# Pinguino4550.net
KiCad netlist of a schematic drawn in EAGLE
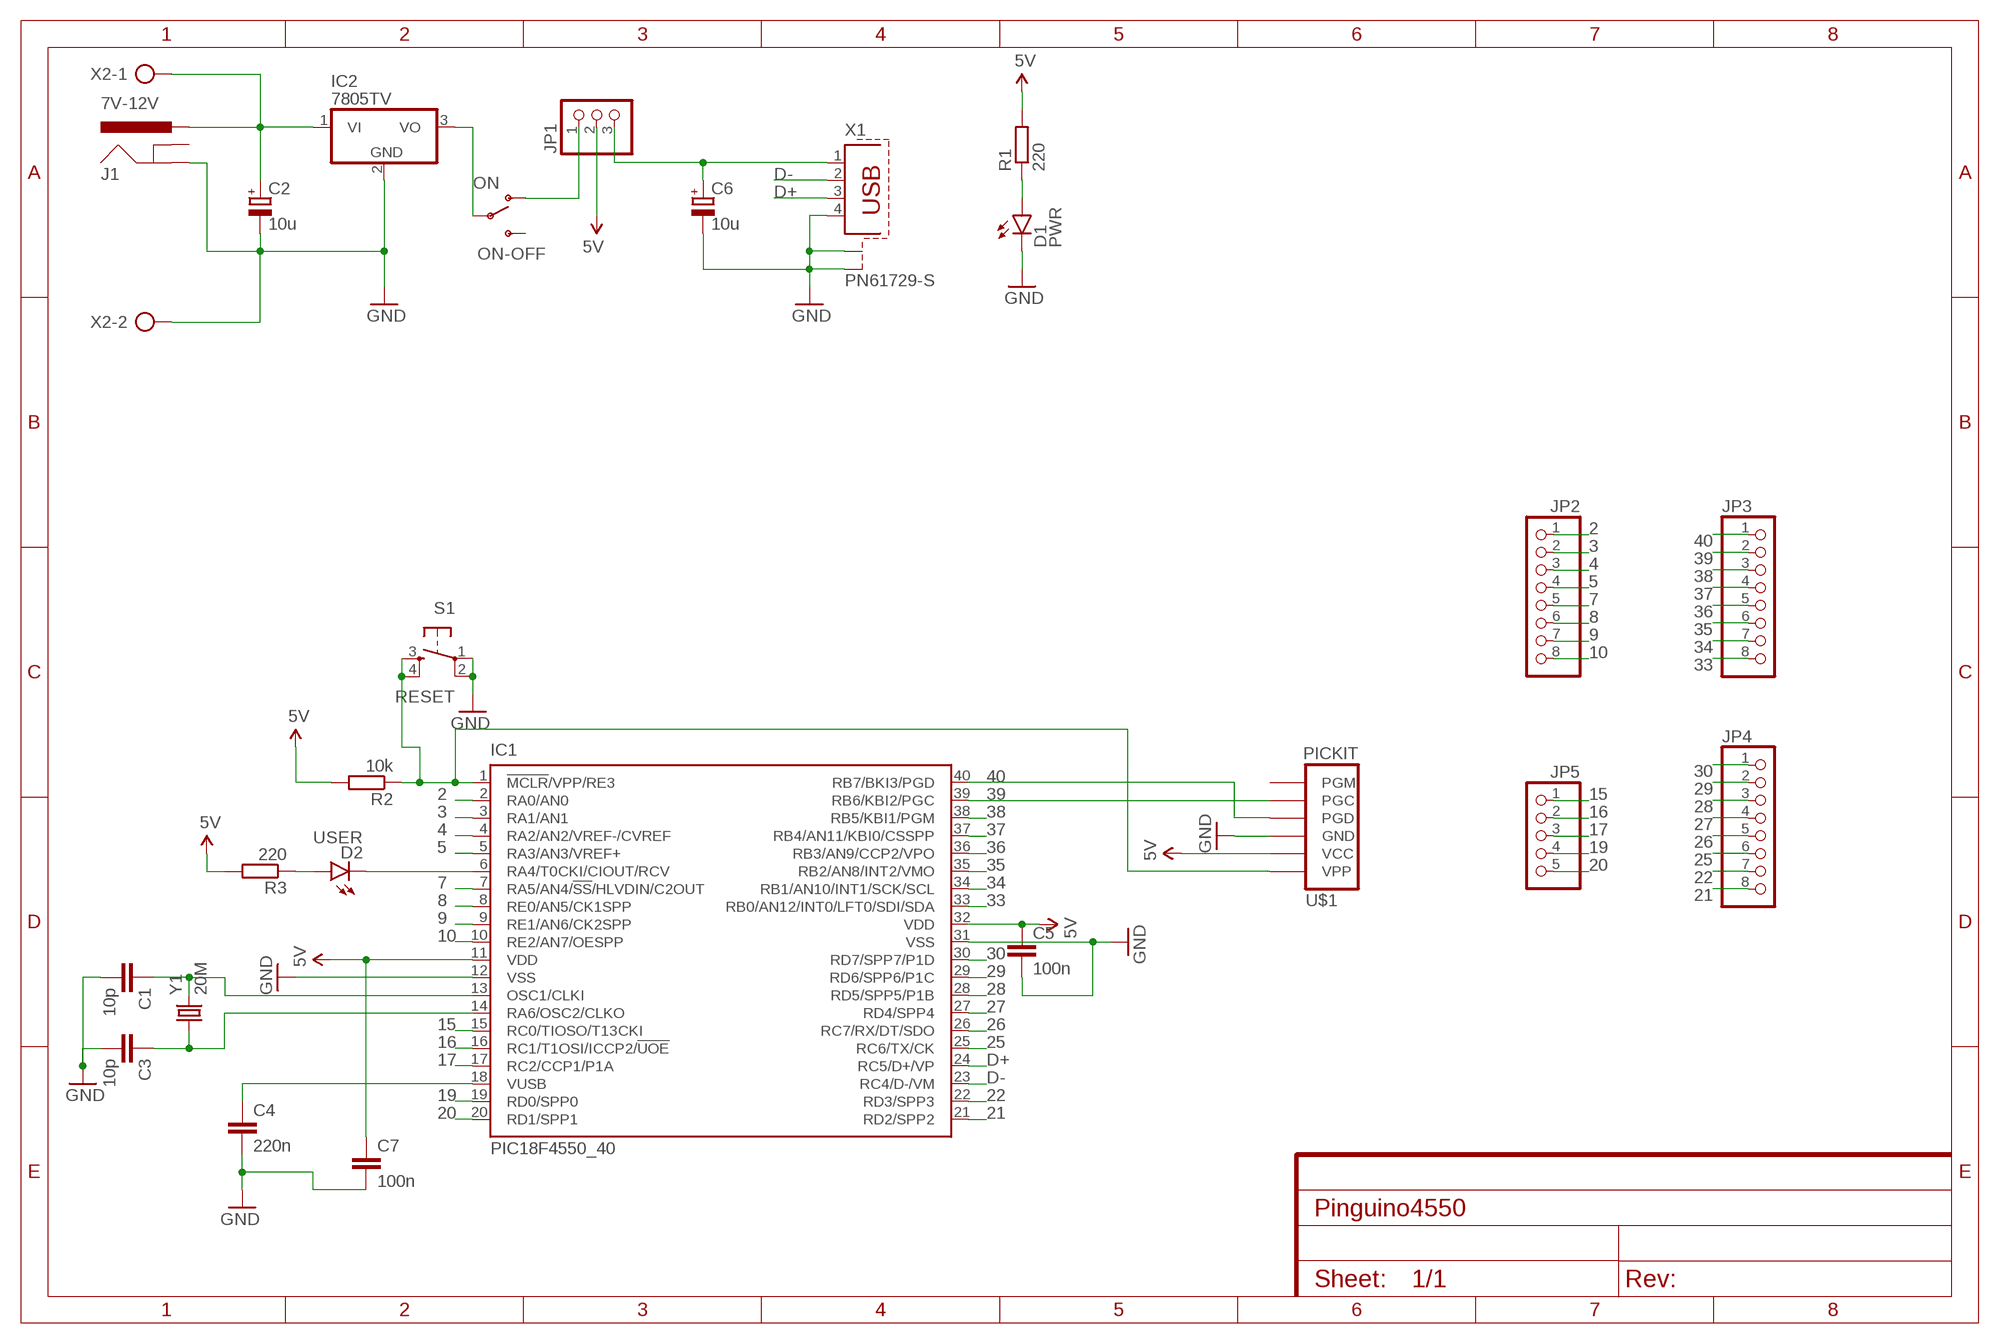
[diagram p0: schematic, sheet 1]

(export (version "E")
  (design (tool "Eeschema 10.0.6"))
  (components
    (comp (ref "C1")
      (value "10p")
      (footprint "eagle-import:C025-030X050")
      (libsource (lib "eagle-import") (part "C-EU025-030X050"))
    )
    (comp (ref "C2")
      (value "10u")
      (footprint "eagle-import:E2,5-5")
      (libsource (lib "eagle-import") (part "CPOL-EUE2.5-5"))
    )
    (comp (ref "C3")
      (value "10p")
      (footprint "eagle-import:C025-030X050")
      (libsource (lib "eagle-import") (part "C-EU025-030X050"))
    )
    (comp (ref "C4")
      (value "220n")
      (footprint "eagle-import:C025-030X050")
      (libsource (lib "eagle-import") (part "C-EU025-030X050"))
    )
    (comp (ref "C5")
      (value "100n")
      (footprint "eagle-import:C025-030X050")
      (libsource (lib "eagle-import") (part "C-EU025-030X050"))
    )
    (comp (ref "C6")
      (value "10u")
      (footprint "eagle-import:E2,5-5")
      (libsource (lib "eagle-import") (part "CPOL-EUE2.5-5"))
    )
    (comp (ref "C7")
      (value "100n")
      (footprint "eagle-import:C025-030X050")
      (libsource (lib "eagle-import") (part "C-EU025-030X050"))
    )
    (comp (ref "D1")
      (value "PWR")
      (footprint "eagle-import:LED5MM")
      (libsource (lib "eagle-import") (part "LED5MM"))
    )
    (comp (ref "D2")
      (value "USER")
      (footprint "eagle-import:LED5MM")
      (libsource (lib "eagle-import") (part "LED5MM"))
    )
    (comp (ref "IC1")
      (value "PIC18F4550_40")
      (footprint "eagle-import:DIL40")
      (fields (field (name "MF") "MICROCHIP") (field (name "MPN") "PIC18F4550-I/P"))
      (libsource (lib "eagle-import") (part "PIC18F4_40550"))
    )
    (comp (ref "IC2")
      (value "7805TV")
      (footprint "eagle-import:TO220V")
      (libsource (lib "eagle-import") (part "78TV05"))
    )
    (comp (ref "J1")
      (value "7V-12V")
      (footprint "eagle-import:POWER_JACK_SLOT")
      (libsource (lib "eagle-import") (part "POWER_JACKSLT"))
    )
    (comp (ref "JP1")
      (value "PINHD-1X3")
      (footprint "eagle-import:1X03")
      (libsource (lib "eagle-import") (part "PINHD-1X3"))
    )
    (comp (ref "JP2")
      (value "PINHD-1X8")
      (footprint "eagle-import:1X08")
      (libsource (lib "eagle-import") (part "PINHD-1X8"))
    )
    (comp (ref "JP3")
      (value "PINHD-1X8")
      (footprint "eagle-import:1X08")
      (libsource (lib "eagle-import") (part "PINHD-1X8"))
    )
    (comp (ref "JP4")
      (value "PINHD-1X8")
      (footprint "eagle-import:1X08")
      (libsource (lib "eagle-import") (part "PINHD-1X8"))
    )
    (comp (ref "JP5")
      (value "PINHD-1X5")
      (footprint "eagle-import:1X05")
      (libsource (lib "eagle-import") (part "PINHD-1X5"))
    )
    (comp (ref "ON-OFF")
      (value "ON")
      (footprint "eagle-import:SWITCH-SPDT")
      (libsource (lib "eagle-import") (part "SWITCH-SPDTPTH"))
    )
    (comp (ref "R1")
      (value "220")
      (footprint "eagle-import:0207_7")
      (libsource (lib "eagle-import") (part "R-EU_0207/7"))
    )
    (comp (ref "R2")
      (value "10k")
      (footprint "eagle-import:0207_7")
      (libsource (lib "eagle-import") (part "R-EU_0207/7"))
    )
    (comp (ref "R3")
      (value "220")
      (footprint "eagle-import:0207_7")
      (libsource (lib "eagle-import") (part "R-EU_0207/7"))
    )
    (comp (ref "S1")
      (value "RESET")
      (footprint "eagle-import:TACTILE-PTH")
      (libsource (lib "eagle-import") (part "TAC_SWITCHPTH"))
    )
    (comp (ref "U$1")
      (value "PICKIT")
      (footprint "eagle-import:MOLEX-1X6_LOCK")
      (libsource (lib "eagle-import") (part "PIC-ICSPPOLAR_LOCK"))
    )
    (comp (ref "X1")
      (value "PN61729-S")
      (footprint "eagle-import:PN61729-S")
      (libsource (lib "eagle-import") (part "PN61729-S"))
    )
    (comp (ref "X2")
      (value "AK500/2")
      (footprint "eagle-import:AK500_2")
      (libsource (lib "eagle-import") (part "AK500/2"))
    )
    (comp (ref "Y1")
      (value "20M")
      (footprint "eagle-import:HC49US")
      (libsource (lib "eagle-import") (part "CRYSTALHC49US"))
    )
  )
  (nets
    (net (code "1") (name "/2") (class "Default")
      (node (ref "IC1") (pin "2") (pinfunction "RA0/AN0_2") (pintype "bidirectional"))
      (node (ref "JP2") (pin "1") (pinfunction "1_1") (pintype "passive"))
    )
    (net (code "2") (name "/3") (class "Default")
      (node (ref "IC1") (pin "3") (pinfunction "RA1/AN1_3") (pintype "bidirectional"))
      (node (ref "JP2") (pin "2") (pinfunction "2_2") (pintype "passive"))
    )
    (net (code "3") (name "/4") (class "Default")
      (node (ref "IC1") (pin "4") (pinfunction "RA2/AN2/VREF-/CVREF_4") (pintype "bidirectional"))
      (node (ref "JP2") (pin "3") (pinfunction "3_3") (pintype "passive"))
    )
    (net (code "4") (name "/5") (class "Default")
      (node (ref "IC1") (pin "5") (pinfunction "RA3/AN3/VREF+_5") (pintype "bidirectional"))
      (node (ref "JP2") (pin "4") (pinfunction "4_4") (pintype "passive"))
    )
    (net (code "5") (name "/7") (class "Default")
      (node (ref "IC1") (pin "7") (pinfunction "RA5/AN4/~{SS}/HLVDIN/C2OUT_7") (pintype "bidirectional"))
      (node (ref "JP2") (pin "5") (pinfunction "5_5") (pintype "passive"))
    )
    (net (code "6") (name "/8") (class "Default")
      (node (ref "IC1") (pin "8") (pinfunction "RE0/AN5/CK1SPP_8") (pintype "bidirectional"))
      (node (ref "JP2") (pin "6") (pinfunction "6_6") (pintype "passive"))
    )
    (net (code "7") (name "/9") (class "Default")
      (node (ref "IC1") (pin "9") (pinfunction "RE1/AN6/CK2SPP_9") (pintype "bidirectional"))
      (node (ref "JP2") (pin "7") (pinfunction "7_7") (pintype "passive"))
    )
    (net (code "8") (name "/10") (class "Default")
      (node (ref "IC1") (pin "10") (pinfunction "RE2/AN7/OESPP_10") (pintype "bidirectional"))
      (node (ref "JP2") (pin "8") (pinfunction "8_8") (pintype "passive"))
    )
    (net (code "9") (name "/15") (class "Default")
      (node (ref "IC1") (pin "15") (pinfunction "RC0/TIOSO/T13CKI_15") (pintype "bidirectional"))
      (node (ref "JP5") (pin "1") (pinfunction "1_1") (pintype "passive"))
    )
    (net (code "10") (name "/16") (class "Default")
      (node (ref "IC1") (pin "16") (pinfunction "RC1/T1OSI/ICCP2/~{UOE}_16") (pintype "bidirectional"))
      (node (ref "JP5") (pin "2") (pinfunction "2_2") (pintype "passive"))
    )
    (net (code "11") (name "/17") (class "Default")
      (node (ref "IC1") (pin "17") (pinfunction "RC2/CCP1/P1A_17") (pintype "bidirectional"))
      (node (ref "JP5") (pin "3") (pinfunction "3_3") (pintype "passive"))
    )
    (net (code "12") (name "/19") (class "Default")
      (node (ref "IC1") (pin "19") (pinfunction "RD0/SPP0_19") (pintype "bidirectional"))
      (node (ref "JP5") (pin "4") (pinfunction "4_4") (pintype "passive"))
    )
    (net (code "13") (name "/20") (class "Default")
      (node (ref "IC1") (pin "20") (pinfunction "RD1/SPP1_20") (pintype "bidirectional"))
      (node (ref "JP5") (pin "5") (pinfunction "5_5") (pintype "passive"))
    )
    (net (code "14") (name "/21") (class "Default")
      (node (ref "IC1") (pin "21") (pinfunction "RD2/SPP2_21") (pintype "bidirectional"))
      (node (ref "JP4") (pin "8") (pinfunction "8_8") (pintype "passive"))
    )
    (net (code "15") (name "/22") (class "Default")
      (node (ref "IC1") (pin "22") (pinfunction "RD3/SPP3_22") (pintype "bidirectional"))
      (node (ref "JP4") (pin "7") (pinfunction "7_7") (pintype "passive"))
    )
    (net (code "16") (name "/25") (class "Default")
      (node (ref "IC1") (pin "25") (pinfunction "RC6/TX/CK_25") (pintype "bidirectional"))
      (node (ref "JP4") (pin "6") (pinfunction "6_6") (pintype "passive"))
    )
    (net (code "17") (name "/26") (class "Default")
      (node (ref "IC1") (pin "26") (pinfunction "RC7/RX/DT/SDO_26") (pintype "bidirectional"))
      (node (ref "JP4") (pin "5") (pinfunction "5_5") (pintype "passive"))
    )
    (net (code "18") (name "/27") (class "Default")
      (node (ref "IC1") (pin "27") (pinfunction "RD4/SPP4_27") (pintype "bidirectional"))
      (node (ref "JP4") (pin "4") (pinfunction "4_4") (pintype "passive"))
    )
    (net (code "19") (name "/28") (class "Default")
      (node (ref "IC1") (pin "28") (pinfunction "RD5/SPP5/P1B_28") (pintype "bidirectional"))
      (node (ref "JP4") (pin "3") (pinfunction "3_3") (pintype "passive"))
    )
    (net (code "20") (name "/29") (class "Default")
      (node (ref "IC1") (pin "29") (pinfunction "RD6/SPP6/P1C_29") (pintype "bidirectional"))
      (node (ref "JP4") (pin "2") (pinfunction "2_2") (pintype "passive"))
    )
    (net (code "21") (name "/30") (class "Default")
      (node (ref "IC1") (pin "30") (pinfunction "RD7/SPP7/P1D_30") (pintype "bidirectional"))
      (node (ref "JP4") (pin "1") (pinfunction "1_1") (pintype "passive"))
    )
    (net (code "22") (name "/33") (class "Default")
      (node (ref "IC1") (pin "33") (pinfunction "RB0/AN12/INT0/LFT0/SDI/SDA_33") (pintype "bidirectional"))
      (node (ref "JP3") (pin "8") (pinfunction "8_8") (pintype "passive"))
    )
    (net (code "23") (name "/34") (class "Default")
      (node (ref "IC1") (pin "34") (pinfunction "RB1/AN10/INT1/SCK/SCL_34") (pintype "bidirectional"))
      (node (ref "JP3") (pin "7") (pinfunction "7_7") (pintype "passive"))
    )
    (net (code "24") (name "/35") (class "Default")
      (node (ref "IC1") (pin "35") (pinfunction "RB2/AN8/INT2/VMO_35") (pintype "bidirectional"))
      (node (ref "JP3") (pin "6") (pinfunction "6_6") (pintype "passive"))
    )
    (net (code "25") (name "/36") (class "Default")
      (node (ref "IC1") (pin "36") (pinfunction "RB3/AN9/CCP2/VPO_36") (pintype "bidirectional"))
      (node (ref "JP3") (pin "5") (pinfunction "5_5") (pintype "passive"))
    )
    (net (code "26") (name "/37") (class "Default")
      (node (ref "IC1") (pin "37") (pinfunction "RB4/AN11/KBI0/CSSPP_37") (pintype "bidirectional"))
      (node (ref "JP3") (pin "4") (pinfunction "4_4") (pintype "passive"))
    )
    (net (code "27") (name "/38") (class "Default")
      (node (ref "IC1") (pin "38") (pinfunction "RB5/KBI1/PGM_38") (pintype "bidirectional"))
      (node (ref "JP3") (pin "3") (pinfunction "3_3") (pintype "passive"))
    )
    (net (code "28") (name "/39") (class "Default")
      (node (ref "IC1") (pin "39") (pinfunction "RB6/KBI2/PGC_39") (pintype "bidirectional"))
      (node (ref "JP3") (pin "2") (pinfunction "2_2") (pintype "passive"))
      (node (ref "U$1") (pin "2") (pinfunction "PGC_2") (pintype "bidirectional"))
    )
    (net (code "29") (name "/40") (class "Default")
      (node (ref "IC1") (pin "40") (pinfunction "RB7/BKI3/PGD_40") (pintype "bidirectional"))
      (node (ref "JP3") (pin "1") (pinfunction "1_1") (pintype "passive"))
      (node (ref "U$1") (pin "3") (pinfunction "PGD_3") (pintype "bidirectional"))
    )
    (net (code "30") (name "/D+") (class "Default")
      (node (ref "IC1") (pin "24") (pinfunction "RC5/D+/VP_24") (pintype "bidirectional"))
      (node (ref "X1") (pin "3") (pinfunction "3_3") (pintype "passive"))
    )
    (net (code "31") (name "/D-") (class "Default")
      (node (ref "IC1") (pin "23") (pinfunction "RC4/D-/VM_23") (pintype "bidirectional"))
      (node (ref "X1") (pin "2") (pinfunction "2_2") (pintype "passive"))
    )
    (net (code "32") (name "5V") (class "Default")
      (node (ref "C5") (pin "1") (pinfunction "1_1") (pintype "passive"))
      (node (ref "C7") (pin "1") (pinfunction "1_1") (pintype "passive"))
      (node (ref "IC1") (pin "11") (pinfunction "VDD_11") (pintype "power_in"))
      (node (ref "IC1") (pin "32") (pinfunction "VDD_32") (pintype "power_in"))
      (node (ref "JP1") (pin "2") (pinfunction "2_2") (pintype "passive"))
      (node (ref "R1") (pin "2") (pinfunction "2_2") (pintype "passive"))
      (node (ref "R2") (pin "2") (pinfunction "2_2") (pintype "passive"))
      (node (ref "R3") (pin "2") (pinfunction "2_2") (pintype "passive"))
      (node (ref "U$1") (pin "5") (pinfunction "VCC_5") (pintype "bidirectional"))
    )
    (net (code "33") (name "GND") (class "Default")
      (node (ref "C1") (pin "2") (pinfunction "2_2") (pintype "passive"))
      (node (ref "C2") (pin "-") (pinfunction "-_-") (pintype "passive"))
      (node (ref "C3") (pin "2") (pinfunction "2_2") (pintype "passive"))
      (node (ref "C4") (pin "2") (pinfunction "2_2") (pintype "passive"))
      (node (ref "C5") (pin "2") (pinfunction "2_2") (pintype "passive"))
      (node (ref "C6") (pin "-") (pinfunction "-_-") (pintype "passive"))
      (node (ref "C7") (pin "2") (pinfunction "2_2") (pintype "passive"))
      (node (ref "D1") (pin "K") (pinfunction "C_K") (pintype "passive"))
      (node (ref "IC1") (pin "12") (pinfunction "VSS_12") (pintype "power_in"))
      (node (ref "IC1") (pin "31") (pinfunction "VSS_31") (pintype "power_in"))
      (node (ref "IC2") (pin "2") (pinfunction "GND_2") (pintype "passive"))
      (node (ref "J1") (pin "GND@2") (pinfunction "GND_GND@2") (pintype "bidirectional"))
      (node (ref "S1") (pin "1") (pinfunction "1_1") (pintype "passive"))
      (node (ref "S1") (pin "2") (pinfunction "2_2") (pintype "passive"))
      (node (ref "U$1") (pin "4") (pinfunction "GND_4") (pintype "bidirectional"))
      (node (ref "X1") (pin "4") (pinfunction "4_4") (pintype "passive"))
      (node (ref "X1") (pin "S1") (pinfunction "S1_S1") (pintype "passive"))
      (node (ref "X1") (pin "S2") (pinfunction "S2_S2") (pintype "passive"))
      (node (ref "X2") (pin "2") (pinfunction "KL_2") (pintype "passive"))
    )
    (net (code "34") (name "Net-(C6-Pad+)") (class "Default")
      (node (ref "C6") (pin "+") (pinfunction "+_+") (pintype "passive"))
      (node (ref "JP1") (pin "3") (pinfunction "3_3") (pintype "passive"))
      (node (ref "X1") (pin "1") (pinfunction "1_1") (pintype "passive"))
    )
    (net (code "35") (name "Net-(D1-PadA)") (class "Default")
      (node (ref "D1") (pin "A") (pinfunction "A_A") (pintype "passive"))
      (node (ref "R1") (pin "1") (pinfunction "1_1") (pintype "passive"))
    )
    (net (code "36") (name "Net-(D2-C)") (class "Default")
      (node (ref "D2") (pin "K") (pinfunction "C_K") (pintype "passive"))
      (node (ref "IC1") (pin "6") (pinfunction "RA4/T0CKI/CIOUT/RCV_6") (pintype "bidirectional"))
    )
    (net (code "37") (name "Net-(D2-PadA)") (class "Default")
      (node (ref "D2") (pin "A") (pinfunction "A_A") (pintype "passive"))
      (node (ref "R3") (pin "1") (pinfunction "1_1") (pintype "passive"))
    )
    (net (code "38") (name "Net-(IC1-OSC1{slash}CLKI)") (class "Default")
      (node (ref "C1") (pin "1") (pinfunction "1_1") (pintype "passive"))
      (node (ref "IC1") (pin "13") (pinfunction "OSC1/CLKI_13") (pintype "input"))
      (node (ref "Y1") (pin "2") (pinfunction "2_2") (pintype "passive"))
    )
    (net (code "39") (name "Net-(IC1-RA6{slash}OSC2{slash}CLKO)") (class "Default")
      (node (ref "C3") (pin "1") (pinfunction "1_1") (pintype "passive"))
      (node (ref "IC1") (pin "14") (pinfunction "RA6/OSC2/CLKO_14") (pintype "output"))
      (node (ref "Y1") (pin "1") (pinfunction "1_1") (pintype "passive"))
    )
    (net (code "40") (name "Net-(IC1-VUSB)") (class "Default")
      (node (ref "C4") (pin "1") (pinfunction "1_1") (pintype "passive"))
      (node (ref "IC1") (pin "18") (pinfunction "VUSB_18") (pintype "bidirectional"))
    )
    (net (code "41") (name "Net-(IC1-~{MCLR}{slash}VPP{slash}RE3)") (class "Default")
      (node (ref "IC1") (pin "1") (pinfunction "~{MCLR}/VPP/RE3_1") (pintype "input"))
      (node (ref "R2") (pin "1") (pinfunction "1_1") (pintype "passive"))
      (node (ref "S1") (pin "3") (pinfunction "3_3") (pintype "passive"))
      (node (ref "S1") (pin "4") (pinfunction "4_4") (pintype "passive"))
      (node (ref "U$1") (pin "6") (pinfunction "VPP_6") (pintype "bidirectional"))
    )
    (net (code "42") (name "Net-(IC2-VI)") (class "Default")
      (node (ref "C2") (pin "+") (pinfunction "+_+") (pintype "passive"))
      (node (ref "IC2") (pin "1") (pinfunction "VI_1") (pintype "input"))
      (node (ref "J1") (pin "PWR") (pinfunction "PWR_PWR") (pintype "bidirectional"))
      (node (ref "X2") (pin "1") (pinfunction "KL_1") (pintype "passive"))
    )
    (net (code "43") (name "Net-(IC2-VO)") (class "Default")
      (node (ref "IC2") (pin "3") (pinfunction "VO_3") (pintype "passive"))
      (node (ref "ON-OFF") (pin "2") (pinfunction "P_2") (pintype "passive"))
    )
    (net (code "44") (name "Net-(ON-OFF-O)") (class "Default")
      (node (ref "JP1") (pin "1") (pinfunction "1_1") (pintype "passive"))
      (node (ref "ON-OFF") (pin "1") (pinfunction "O_1") (pintype "passive"))
    )
    (net (code "45") (name "unconnected-(J1-GNDBREAK-PadGND@1)") (class "Default")
      (node (ref "J1") (pin "GND@1") (pinfunction "GNDBREAK_GND@1") (pintype "bidirectional"))
    )
    (net (code "46") (name "unconnected-(ON-OFF-S-Pad3)") (class "Default")
      (node (ref "ON-OFF") (pin "3") (pinfunction "S_3") (pintype "passive"))
    )
    (net (code "47") (name "unconnected-(U$1-PGM-Pad1)") (class "Default")
      (node (ref "U$1") (pin "1") (pinfunction "PGM_1") (pintype "bidirectional"))
    )
  )
)
